# VOLT_CONV_SCH.net
KiCad netlist of a schematic drawn in Altium Designer
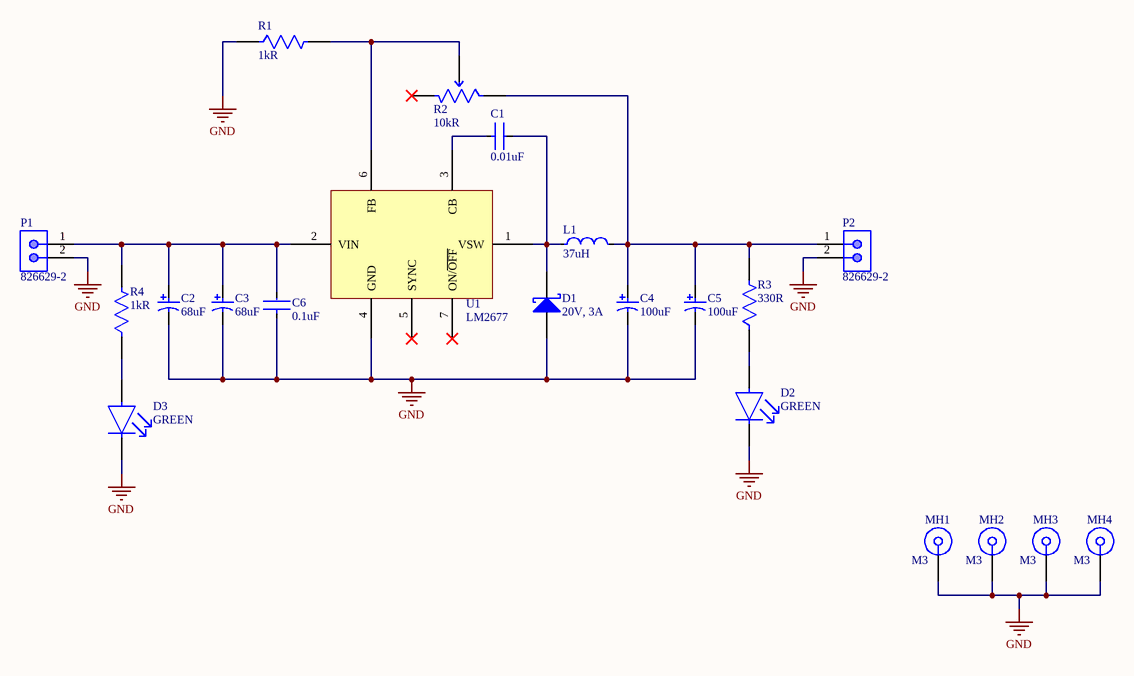
[diagram p0: VOLT_CONV_SCH.SchDoc]

(export (version "E")
  (design (tool "Eeschema 10.0.6"))
  (components
    (comp (ref "C1")
      (value "0.01uF")
      (footprint "CAP_1206_AVX_1206")
      (description "±10% 50V Ceramic Capacitor X7R 1206 (3216 Metric)")
      (fields
        (field (name "MANUFACTURER") "AVX Corporation")
        (field (name "MANUFACTURER PART NUMBER") "12065C103KAT2A")
      )
      (libsource (lib "VOLT_CONV_INT_LIB") (part "CAP_0.01uF_10%_50V"))
    )
    (comp (ref "C2")
      (value "68uF")
      (footprint "CAP_2917_KEMT_T495_D")
      (description "Molded Tantalum Capacitors 2917 (7343 Metric) 300mOhm")
      (fields
        (field (name "MANUFACTURER") "KEMET")
        (field (name "MANUFACTURER PART NUMBER") "T495D686K020ATE300")
      )
      (libsource (lib "VOLT_CONV_INT_LIB") (part "PCAP_68uF_10%_20V"))
    )
    (comp (ref "C3")
      (value "68uF")
      (footprint "CAP_2917_KEMT_T495_D")
      (description "Molded Tantalum Capacitors 2917 (7343 Metric) 300mOhm")
      (fields
        (field (name "MANUFACTURER") "KEMET")
        (field (name "MANUFACTURER PART NUMBER") "T495D686K020ATE300")
      )
      (libsource (lib "VOLT_CONV_INT_LIB") (part "PCAP_68uF_10%_20V"))
    )
    (comp (ref "C4")
      (value "100uF")
      (footprint "CAP_2917_AVX_7343_31")
      (description "Molded Tantalum Capacitors 2917 (7343 Metric) 125mOhm")
      (fields
        (field (name "MANUFACTURER") "AVX Corporation")
        (field (name "MANUFACTURER PART NUMBER") "TPSD107K016R0125")
      )
      (libsource (lib "VOLT_CONV_INT_LIB") (part "PCAP_100uF_10%_16V"))
    )
    (comp (ref "C5")
      (value "100uF")
      (footprint "CAP_2917_AVX_7343_31")
      (description "Molded Tantalum Capacitors 2917 (7343 Metric) 125mOhm")
      (fields
        (field (name "MANUFACTURER") "AVX Corporation")
        (field (name "MANUFACTURER PART NUMBER") "TPSD107K016R0125")
      )
      (libsource (lib "VOLT_CONV_INT_LIB") (part "PCAP_100uF_10%_16V"))
    )
    (comp (ref "C6")
      (value "0.1uF")
      (footprint "CAP_1206_AVX_1206")
      (description "±10% 50V Ceramic Capacitor X8R 1206 (3216 Metric)")
      (fields
        (field (name "MANUFACTURER") "AVX Corporation")
        (field (name "MANUFACTURER PART NUMBER") "12065F104K4T2A")
      )
      (libsource (lib "VOLT_CONV_INT_LIB") (part "CAP_0.1uF_10%_50V"))
    )
    (comp (ref "D1")
      (value "20V, 3A")
      (footprint "DIO_SCHOTTKY_ON_SMC_403AG")
      (description "Diode Schottky 3A Surface Mount SMC (DO-214AB)")
      (fields
        (field (name "MANUFACTURER") "ON Semiconductor")
        (field (name "MANUFACTURER PART NUMBER") "SS32")
      )
      (libsource (lib "VOLT_CONV_INT_LIB") (part "DIO_SCHOTTKY_20V_3A"))
    )
    (comp (ref "D2")
      (value "GREEN")
      (footprint "DIO_1206_ LTST_C150")
      (description "LED GREEN CLEAR CHIP SMD")
      (fields
        (field (name "MANUFACTURER") "Lite-On Inc.")
        (field (name "MANUFACTURER PART NUMBER") "LTST-C150GKT")
      )
      (libsource (lib "VOLT_CONV_INT_LIB") (part "DIO_LED_GREEN"))
    )
    (comp (ref "D3")
      (value "GREEN")
      (footprint "DIO_1206_ LTST_C150")
      (description "LED GREEN CLEAR CHIP SMD")
      (fields
        (field (name "MANUFACTURER") "Lite-On Inc.")
        (field (name "MANUFACTURER PART NUMBER") "LTST-C150GKT")
      )
      (libsource (lib "VOLT_CONV_INT_LIB") (part "DIO_LED_GREEN"))
    )
    (comp (ref "L1")
      (value "37uH")
      (footprint "IND_NON_STD_LCI44")
      (description "Shielded Toroidal Inductor 100mOhm Nonstandard")
      (fields
        (field (name "MANUFACTURER") "Pulse Electronics Power")
        (field (name "MANUFACTURER PART NUMBER") "PE-53932SNL")
      )
      (libsource (lib "VOLT_CONV_INT_LIB") (part "IND_37uH_20%_2.24A"))
    )
    (comp (ref "MH1")
      (value "M3")
      (footprint "MH_M3")
      (description "M3 Mounting Hole")
      (libsource (lib "VOLT_CONV_INT_LIB") (part "MH_M3"))
    )
    (comp (ref "MH2")
      (value "M3")
      (footprint "MH_M3")
      (description "M3 Mounting Hole")
      (libsource (lib "VOLT_CONV_INT_LIB") (part "MH_M3"))
    )
    (comp (ref "MH3")
      (value "M3")
      (footprint "MH_M3")
      (description "M3 Mounting Hole")
      (libsource (lib "VOLT_CONV_INT_LIB") (part "MH_M3"))
    )
    (comp (ref "MH4")
      (value "M3")
      (footprint "MH_M3")
      (description "M3 Mounting Hole")
      (libsource (lib "VOLT_CONV_INT_LIB") (part "MH_M3"))
    )
    (comp (ref "P1")
      (value "826629-2")
      (footprint "CONN_HEADER_MALE_0.1_2x1")
      (description "CONN HEADER VERT 2POS 2.54MM")
      (fields (field (name "MANUFACTURER") "TE Connectivity AMP Connectors"))
      (libsource (lib "VOLT_CONV_INT_LIB") (part "CONN_VERT_HEADER_MALE_0.1_2x1"))
    )
    (comp (ref "P2")
      (value "826629-2")
      (footprint "CONN_HEADER_MALE_0.1_2x1")
      (description "CONN HEADER VERT 2POS 2.54MM")
      (fields (field (name "MANUFACTURER") "TE Connectivity AMP Connectors"))
      (libsource (lib "") (part "CONN_VERT_HEADER_MALE_0.1_2x1_1"))
    )
    (comp (ref "R1")
      (value "1kR")
      (footprint "RES_1206_YAGEO_RC_1206")
      (description "±1% 0.25W, 1/4W Chip Resistor 1206 (3216 Metric) Moisture Resistant Thick Film")
      (fields
        (field (name "MANUFACTURER") "Yageo")
        (field (name "MANUFACTURER PART NUMBER") "RC1206FR-071KL")
      )
      (libsource (lib "VOLT_CONV_INT_LIB") (part "RES_1kR_1%_0.25W"))
    )
    (comp (ref "R2")
      (value "10kR")
      (footprint "RES_VAR_BRN_3214X")
      (description "0.25W, 1/4W Gull Wing Surface Mount Trimmer Potentiometer Cermet Turn Top Adjustment")
      (fields
        (field (name "MANUFACTURER") "Bourns Inc.")
        (field (name "MANUFACTURER PART NUMBER") "3214X-1-103E")
      )
      (libsource (lib "VOLT_CONV_INT_LIB") (part "RES_VAR_10kR_10%_0.25W"))
    )
    (comp (ref "R3")
      (value "330R")
      (footprint "RES_1206_SE_RMCF1206")
      (description "±5% 0.25W, 1/4W Chip Resistor 1206 (3216 Metric) Automotive AEC-Q200 Thick Film")
      (fields
        (field (name "MANUFACTURER") "Stackpole Electronics Inc")
        (field (name "MANUFACTURER PART NUMBER") "RMCF1206JT330R")
      )
      (libsource (lib "VOLT_CONV_INT_LIB") (part "RES_330R_5%_0.25W"))
    )
    (comp (ref "R4")
      (value "1kR")
      (footprint "RES_1206_YAGEO_RC_1206")
      (description "±1% 0.25W, 1/4W Chip Resistor 1206 (3216 Metric) Moisture Resistant Thick Film")
      (fields
        (field (name "MANUFACTURER") "Yageo")
        (field (name "MANUFACTURER PART NUMBER") "RC1206FR-071KL")
      )
      (libsource (lib "VOLT_CONV_INT_LIB") (part "RES_1kR_1%_0.25W"))
    )
    (comp (ref "U1")
      (value "LM2677")
      (footprint "IC_TO_263_7_KTW0007B")
      (fields
        (field (name "MANUFACTURER") "Texas Instruments")
        (field (name "MANUFACTURER PART NUMBER") "LM2677S-ADJ/NOPB")
      )
      (libsource (lib "VOLT_CONV_INT_LIB") (part "IC_LM2677"))
    )
  )
  (nets
    (net (code "1") (name "GND") (class "Default")
      (node (ref "C2") (pin "2") (pinfunction "2_2") (pintype "passive"))
      (node (ref "C3") (pin "2") (pinfunction "2_2") (pintype "passive"))
      (node (ref "C4") (pin "2") (pinfunction "2_2") (pintype "passive"))
      (node (ref "C5") (pin "2") (pinfunction "2_2") (pintype "passive"))
      (node (ref "C6") (pin "1") (pinfunction "1_1") (pintype "passive"))
      (node (ref "D1") (pin "A") (pinfunction "A_A") (pintype "passive"))
      (node (ref "D2") (pin "2") (pinfunction "2_2") (pintype "passive"))
      (node (ref "D3") (pin "2") (pinfunction "2_2") (pintype "passive"))
      (node (ref "MH1") (pin "1") (pinfunction "1_1") (pintype "passive"))
      (node (ref "MH2") (pin "1") (pinfunction "1_1") (pintype "passive"))
      (node (ref "MH3") (pin "1") (pinfunction "1_1") (pintype "passive"))
      (node (ref "MH4") (pin "1") (pinfunction "1_1") (pintype "passive"))
      (node (ref "P1") (pin "2") (pinfunction "2_2") (pintype "passive"))
      (node (ref "P2") (pin "2") (pinfunction "2_2") (pintype "passive"))
      (node (ref "R1") (pin "1") (pinfunction "1_1") (pintype "passive"))
      (node (ref "U1") (pin "4") (pinfunction "GND_4") (pintype "passive"))
    )
    (net (code "2") (name "Net-(D2-Pad1)") (class "Default")
      (node (ref "D2") (pin "1") (pinfunction "1_1") (pintype "passive"))
      (node (ref "R3") (pin "1") (pinfunction "1_1") (pintype "passive"))
    )
    (net (code "3") (name "Net-(D3-Pad1)") (class "Default")
      (node (ref "D3") (pin "1") (pinfunction "1_1") (pintype "passive"))
      (node (ref "R4") (pin "1") (pinfunction "1_1") (pintype "passive"))
    )
    (net (code "4") (name "Net-(R2-CCW)") (class "Default")
      (node (ref "C4") (pin "1") (pinfunction "1_1") (pintype "passive"))
      (node (ref "C5") (pin "1") (pinfunction "1_1") (pintype "passive"))
      (node (ref "L1") (pin "2") (pinfunction "2_2") (pintype "passive"))
      (node (ref "P2") (pin "1") (pinfunction "1_1") (pintype "passive"))
      (node (ref "R2") (pin "1") (pinfunction "CCW_1") (pintype "passive"))
      (node (ref "R3") (pin "2") (pinfunction "2_2") (pintype "passive"))
    )
    (net (code "5") (name "Net-(R2-WIPER)") (class "Default")
      (node (ref "R1") (pin "2") (pinfunction "2_2") (pintype "passive"))
      (node (ref "R2") (pin "2") (pinfunction "WIPER_2") (pintype "passive"))
      (node (ref "U1") (pin "6") (pinfunction "FB_6") (pintype "passive"))
    )
    (net (code "6") (name "Net-(U1-CB)") (class "Default")
      (node (ref "C1") (pin "1") (pinfunction "1_1") (pintype "passive"))
      (node (ref "U1") (pin "3") (pinfunction "CB_3") (pintype "passive"))
    )
    (net (code "7") (name "Net-(U1-VIN)") (class "Default")
      (node (ref "C2") (pin "1") (pinfunction "1_1") (pintype "passive"))
      (node (ref "C3") (pin "1") (pinfunction "1_1") (pintype "passive"))
      (node (ref "C6") (pin "2") (pinfunction "2_2") (pintype "passive"))
      (node (ref "P1") (pin "1") (pinfunction "1_1") (pintype "passive"))
      (node (ref "R4") (pin "2") (pinfunction "2_2") (pintype "passive"))
      (node (ref "U1") (pin "2") (pinfunction "VIN_2") (pintype "passive"))
    )
    (net (code "8") (name "Net-(U1-VSW)") (class "Default")
      (node (ref "C1") (pin "2") (pinfunction "2_2") (pintype "passive"))
      (node (ref "D1") (pin "K") (pinfunction "K_K") (pintype "passive"))
      (node (ref "L1") (pin "1") (pinfunction "1_1") (pintype "passive"))
      (node (ref "U1") (pin "1") (pinfunction "VSW_1") (pintype "passive"))
    )
    (net (code "9") (name "unconnected-(R2-CW-Pad3)") (class "Default")
      (node (ref "R2") (pin "3") (pinfunction "CW_3") (pintype "passive+no_connect"))
    )
    (net (code "10") (name "unconnected-(U1-ON{slash}~{OFF}-Pad7)") (class "Default")
      (node (ref "U1") (pin "7") (pinfunction "ON/~{OFF}_7") (pintype "passive+no_connect"))
    )
    (net (code "11") (name "unconnected-(U1-SYNC-Pad5)") (class "Default")
      (node (ref "U1") (pin "5") (pinfunction "SYNC_5") (pintype "passive+no_connect"))
    )
  )
)
